# 1-Schematic_pcbhackerboard.net
KiCad netlist of a schematic drawn in EasyEDA
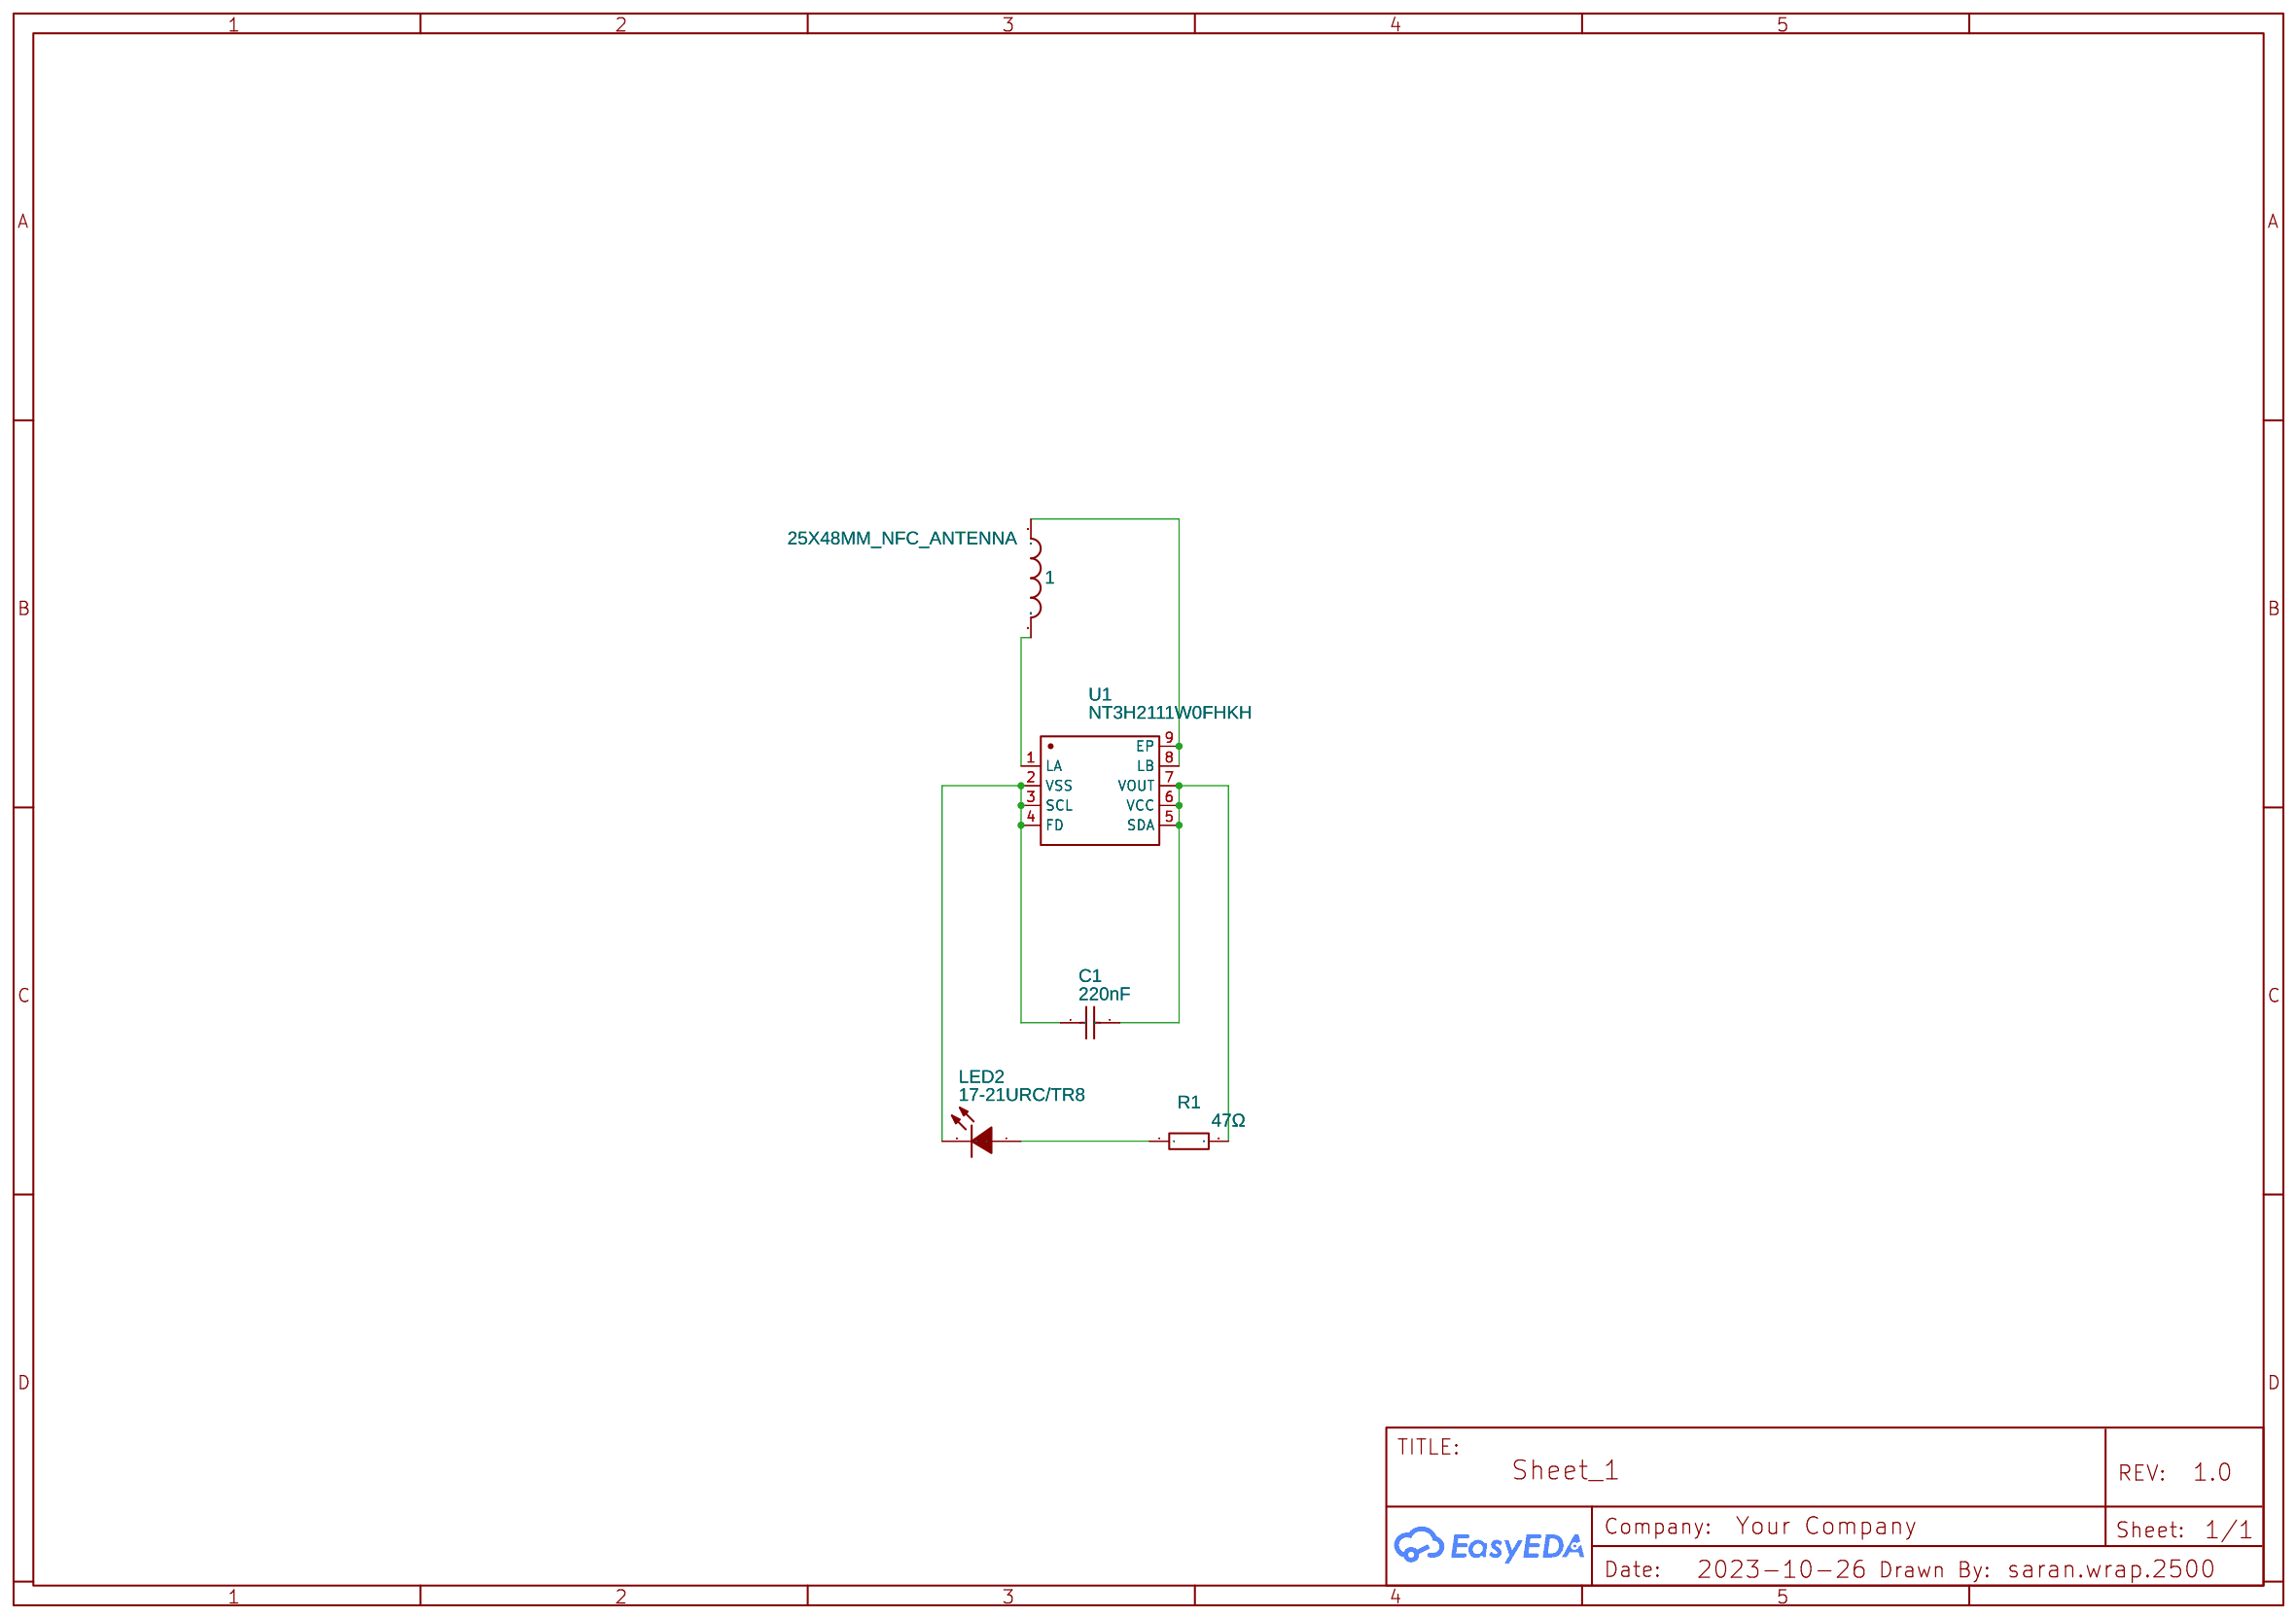
[diagram p0: schematic sheet]

(export (version "E")
  (design (tool "Eeschema 10.0.6"))
  (components
    (comp (ref "1") (value "25X48MM_NFC_ANTENNA") (libsource (lib "") (part "25X48MM_NFC_ANTENNA")))
    (comp (ref "C1")
      (value "220nF")
      (fields
        (field (name "Manufacturer Part") "CL10B224KA8NNNC")
        (field (name "Manufacturer") "SAMSUNG(三星)")
      )
      (libsource (lib "") (part "CL10B224KA8NNNC"))
    )
    (comp (ref "LED2")
      (value "17-21URC/TR8")
      (fields (field (name "Manufacturer") "EVERLIGHT(亿光)"))
      (libsource (lib "") (part "17-21URC/TR8"))
    )
    (comp (ref "R1")
      (value "47Ω")
      (fields
        (field (name "Manufacturer Part") "0603WAF470JT5E")
        (field (name "Manufacturer") "UNI-ROYAL(厚声)")
      )
      (libsource (lib "") (part "0603WAF470JT5E"))
    )
    (comp (ref "U1")
      (value "NT3H2111W0FHKH")
      (fields (field (name "Manufacturer") "NXP(恩智浦)"))
      (libsource (lib "") (part "NT3H2111W0FHKH"))
    )
  )
  (nets
    (net (code "1") (name "Net-(LED2-A)") (class "Default")
      (node (ref "LED2") (pin "1") (pinfunction "A_1") (pintype "unspecified"))
      (node (ref "R1") (pin "1") (pinfunction "1_1") (pintype "input"))
    )
    (net (code "2") (name "Net-(LED2-K)") (class "Default")
      (node (ref "C1") (pin "1") (pinfunction "1_1") (pintype "input"))
      (node (ref "LED2") (pin "2") (pinfunction "K_2") (pintype "unspecified"))
      (node (ref "U1") (pin "2") (pinfunction "VSS_2") (pintype "unspecified"))
      (node (ref "U1") (pin "3") (pinfunction "SCL_3") (pintype "unspecified"))
      (node (ref "U1") (pin "4") (pinfunction "FD_4") (pintype "unspecified"))
    )
    (net (code "3") (name "Net-(U1-EP)") (class "Default")
      (node (ref "1") (pin "P$1") (pinfunction "P$1_P$1") (pintype "bidirectional"))
      (node (ref "U1") (pin "8") (pinfunction "LB_8") (pintype "unspecified"))
      (node (ref "U1") (pin "9") (pinfunction "EP_9") (pintype "unspecified"))
    )
    (net (code "4") (name "Net-(U1-LA)") (class "Default")
      (node (ref "1") (pin "P$2") (pinfunction "P$2_P$2") (pintype "bidirectional"))
      (node (ref "U1") (pin "1") (pinfunction "LA_1") (pintype "unspecified"))
    )
    (net (code "5") (name "Net-(U1-SDA)") (class "Default")
      (node (ref "C1") (pin "2") (pinfunction "2_2") (pintype "input"))
      (node (ref "R1") (pin "2") (pinfunction "2_2") (pintype "input"))
      (node (ref "U1") (pin "5") (pinfunction "SDA_5") (pintype "unspecified"))
      (node (ref "U1") (pin "6") (pinfunction "VCC_6") (pintype "unspecified"))
      (node (ref "U1") (pin "7") (pinfunction "VOUT_7") (pintype "unspecified"))
    )
  )
)
